# cc1101-2ch-dimmer.net
KiCad netlist of a schematic drawn in EAGLE
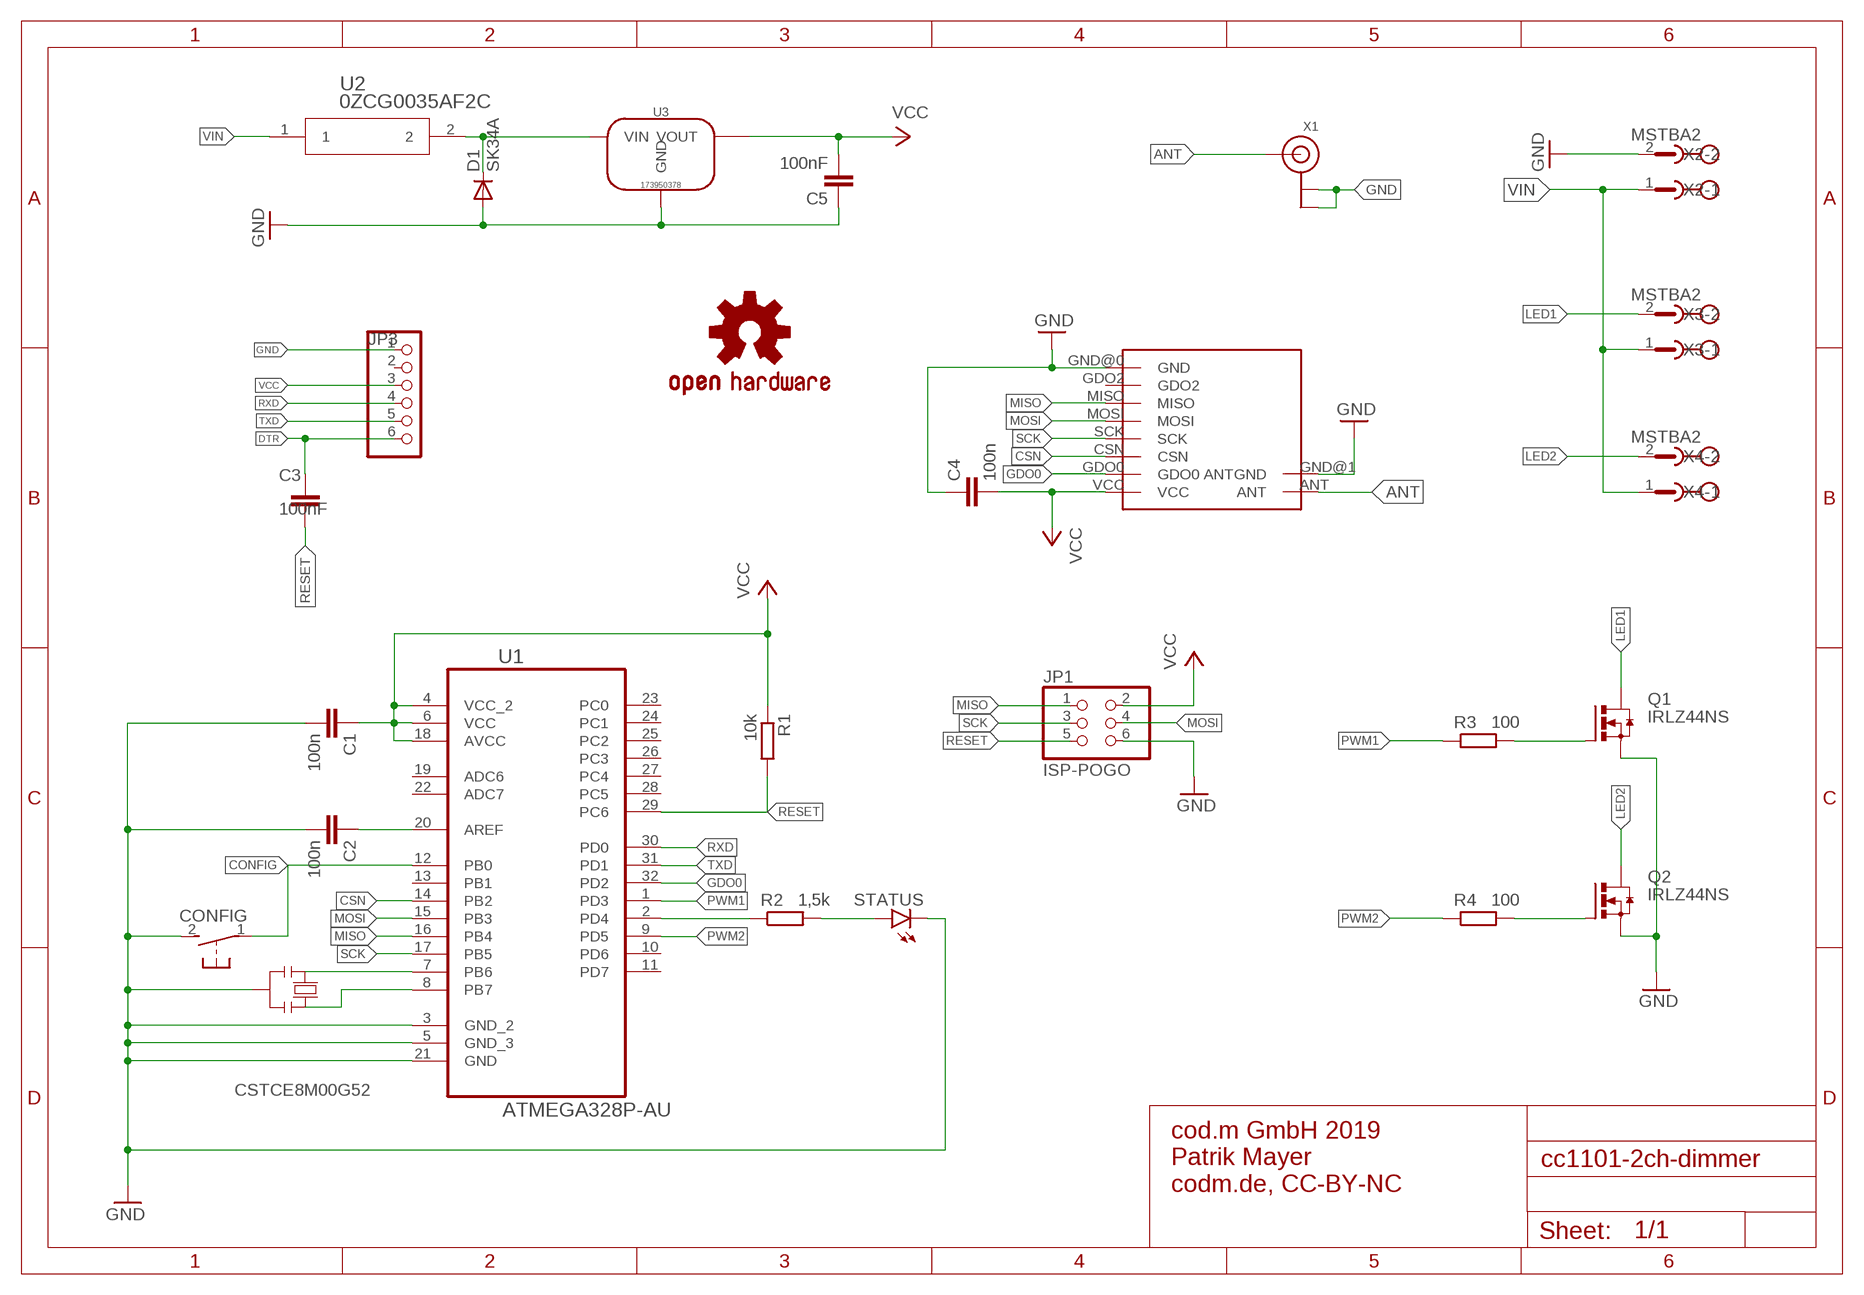
[diagram p0: schematic, sheet 1]

(export (version "E")
  (design (tool "Eeschema 10.0.6"))
  (components
    (comp (ref "C1")
      (value "100n")
      (footprint "eagle-import:C0805")
      (libsource (lib "eagle-import") (part "C-EUC0805"))
    )
    (comp (ref "C2")
      (value "100n")
      (footprint "eagle-import:C0805")
      (libsource (lib "eagle-import") (part "C-EUC0805"))
    )
    (comp (ref "C3")
      (value "100nF")
      (footprint "eagle-import:C0805")
      (libsource (lib "eagle-import") (part "C-EUC0805"))
    )
    (comp (ref "C4")
      (value "100n")
      (footprint "eagle-import:C0805")
      (libsource (lib "eagle-import") (part "C-EUC0805"))
    )
    (comp (ref "C5")
      (value "100nF")
      (footprint "eagle-import:C0805")
      (libsource (lib "eagle-import") (part "C-EUC0805"))
    )
    (comp (ref "CONFIG")
      (value "31-XX")
      (footprint "eagle-import:B3F-31XX")
      (fields (field (name "MPN") "B3F-3100"))
      (libsource (lib "eagle-import") (part "31-XX"))
    )
    (comp (ref "D1")
      (value "SK34A")
      (footprint "eagle-import:DO214AC")
      (libsource (lib "eagle-import") (part "DIODE-DO214AC"))
    )
    (comp (ref "JP1")
      (value "ISP-POGO")
      (footprint "eagle-import:2X03")
      (libsource (lib "eagle-import") (part "PINHD6-CLEAN"))
    )
    (comp (ref "JP3")
      (value "PINHD-1X6")
      (footprint "eagle-import:1X06")
      (libsource (lib "eagle-import") (part "PINHD-1X6"))
    )
    (comp (ref "LOGO1")
      (value "OSHW-LOGOM")
      (footprint "eagle-import:OSHW-LOGO-M")
      (libsource (lib "eagle-import") (part "OSHW-LOGOM"))
    )
    (comp (ref "Q1")
      (value "IRLZ44NS")
      (footprint "eagle-import:D2PAK")
      (libsource (lib "eagle-import") (part "IRLZ44NSD2PAK"))
    )
    (comp (ref "Q2")
      (value "IRLZ44NS")
      (footprint "eagle-import:D2PAK")
      (libsource (lib "eagle-import") (part "IRLZ44NSD2PAK"))
    )
    (comp (ref "R1")
      (value "10k")
      (footprint "eagle-import:R0805")
      (libsource (lib "eagle-import") (part "R-EU_R0805"))
    )
    (comp (ref "R2")
      (value "1,5k")
      (footprint "eagle-import:R0805")
      (libsource (lib "eagle-import") (part "R-EU_R0805"))
    )
    (comp (ref "R3")
      (value "100")
      (footprint "eagle-import:R0805")
      (libsource (lib "eagle-import") (part "R-EU_R0805"))
    )
    (comp (ref "R4")
      (value "100")
      (footprint "eagle-import:R0805")
      (libsource (lib "eagle-import") (part "R-EU_R0805"))
    )
    (comp (ref "STATUS")
      (value "LEDCHIPLED_0805")
      (footprint "eagle-import:CHIPLED_0805")
      (libsource (lib "eagle-import") (part "LEDCHIPLED_0805"))
    )
    (comp (ref "U$1")
      (value "CC1101-868MS10")
      (footprint "eagle-import:CC1101-868MS10")
      (libsource (lib "eagle-import") (part "CC1101-868MS10"))
    )
    (comp (ref "U1")
      (value "ATMEGA328P-AU")
      (footprint "eagle-import:QFP80P900X900X120-32N")
      (libsource (lib "eagle-import") (part "ATMEGA328P-AU"))
    )
    (comp (ref "U2")
      (value "0ZCG0035AF2C")
      (footprint "eagle-import:0ZCG")
      (libsource (lib "eagle-import") (part "0ZCG0035AF2C"))
    )
    (comp (ref "U3")
      (value "173950378")
      (footprint "eagle-import:SIP-3")
      (fields (field (name "MF") "Wurth Electronics"))
      (libsource (lib "eagle-import") (part "173950378"))
    )
    (comp (ref "X1")
      (value "ANTENNA_U.FL")
      (footprint "eagle-import:U.FL")
      (libsource (lib "eagle-import") (part "ANTENNA_U.FL"))
    )
    (comp (ref "X2")
      (value "MSTBA2")
      (footprint "eagle-import:MSTBA2")
      (fields (field (name "MF") "FARNELL") (field (name "MPN") "1757242"))
      (libsource (lib "eagle-import") (part "MSTBA2"))
    )
    (comp (ref "X3")
      (value "MSTBA2")
      (footprint "eagle-import:MSTBA2")
      (fields (field (name "MF") "FARNELL") (field (name "MPN") "1757242"))
      (libsource (lib "eagle-import") (part "MSTBA2"))
    )
    (comp (ref "X4")
      (value "MSTBA2")
      (footprint "eagle-import:MSTBA2")
      (fields (field (name "MF") "FARNELL") (field (name "MPN") "1757242"))
      (libsource (lib "eagle-import") (part "MSTBA2"))
    )
    (comp (ref "Y1")
      (value "CSTCE8M00G52")
      (footprint "eagle-import:RESONATOR")
      (libsource (lib "eagle-import") (part "RESONATORMU"))
    )
  )
  (nets
    (net (code "1") (name "ANT") (class "Default")
      (node (ref "U$1") (pin "ANT") (pinfunction "ANT_ANT") (pintype "bidirectional"))
      (node (ref "X1") (pin "3") (pinfunction "SIGNAL_3") (pintype "passive"))
    )
    (net (code "2") (name "CONFIG") (class "Default")
      (node (ref "CONFIG") (pin "1") (pinfunction "P_1") (pintype "passive"))
      (node (ref "U1") (pin "12") (pinfunction "PB0_12") (pintype "bidirectional"))
    )
    (net (code "3") (name "CSN") (class "Default")
      (node (ref "U$1") (pin "CSN") (pinfunction "CSN_CSN") (pintype "bidirectional"))
      (node (ref "U1") (pin "14") (pinfunction "PB2_14") (pintype "bidirectional"))
    )
    (net (code "4") (name "DTR") (class "Default")
      (node (ref "C3") (pin "1") (pinfunction "1_1") (pintype "passive"))
      (node (ref "JP3") (pin "6") (pinfunction "6_6") (pintype "passive"))
    )
    (net (code "5") (name "GDO0") (class "Default")
      (node (ref "U$1") (pin "GDO0") (pinfunction "GDO0_GDO0") (pintype "bidirectional"))
      (node (ref "U1") (pin "32") (pinfunction "PD2_32") (pintype "bidirectional"))
    )
    (net (code "6") (name "GND") (class "Default")
      (node (ref "C1") (pin "2") (pinfunction "2_2") (pintype "passive"))
      (node (ref "C2") (pin "2") (pinfunction "2_2") (pintype "passive"))
      (node (ref "C4") (pin "1") (pinfunction "1_1") (pintype "passive"))
      (node (ref "C5") (pin "1") (pinfunction "1_1") (pintype "passive"))
      (node (ref "CONFIG") (pin "2") (pinfunction "S_2") (pintype "passive"))
      (node (ref "D1") (pin "A") (pinfunction "A_A") (pintype "passive"))
      (node (ref "JP1") (pin "6") (pinfunction "6_6") (pintype "passive"))
      (node (ref "JP3") (pin "1") (pinfunction "1_1") (pintype "passive"))
      (node (ref "Q1") (pin "3") (pinfunction "S_3") (pintype "passive"))
      (node (ref "Q2") (pin "3") (pinfunction "S_3") (pintype "passive"))
      (node (ref "STATUS") (pin "C") (pinfunction "C_C") (pintype "passive"))
      (node (ref "U$1") (pin "GND@0") (pinfunction "GND_GND@0") (pintype "bidirectional"))
      (node (ref "U$1") (pin "GND@1") (pinfunction "ANTGND_GND@1") (pintype "bidirectional"))
      (node (ref "U1") (pin "21") (pinfunction "GND_21") (pintype "passive"))
      (node (ref "U1") (pin "3") (pinfunction "GND_2_3") (pintype "passive"))
      (node (ref "U1") (pin "5") (pinfunction "GND_3_5") (pintype "passive"))
      (node (ref "U3") (pin "P$2") (pinfunction "GND_P$2") (pintype "bidirectional"))
      (node (ref "X1") (pin "1") (pinfunction "GND_1") (pintype "passive"))
      (node (ref "X1") (pin "2") (pinfunction "GND_2") (pintype "passive"))
      (node (ref "X2") (pin "2") (pinfunction "1_2") (pintype "passive"))
      (node (ref "Y1") (pin "2") (pinfunction "2_2") (pintype "passive"))
    )
    (net (code "7") (name "LED1") (class "Default")
      (node (ref "Q1") (pin "2") (pinfunction "D_2") (pintype "passive"))
      (node (ref "X3") (pin "2") (pinfunction "1_2") (pintype "passive"))
    )
    (net (code "8") (name "LED2") (class "Default")
      (node (ref "Q2") (pin "2") (pinfunction "D_2") (pintype "passive"))
      (node (ref "X4") (pin "2") (pinfunction "1_2") (pintype "passive"))
    )
    (net (code "9") (name "MISO") (class "Default")
      (node (ref "JP1") (pin "1") (pinfunction "1_1") (pintype "passive"))
      (node (ref "U$1") (pin "MISO") (pinfunction "MISO_MISO") (pintype "bidirectional"))
      (node (ref "U1") (pin "16") (pinfunction "PB4_16") (pintype "bidirectional"))
    )
    (net (code "10") (name "MOSI") (class "Default")
      (node (ref "JP1") (pin "4") (pinfunction "4_4") (pintype "passive"))
      (node (ref "U$1") (pin "MOSI") (pinfunction "MOSI_MOSI") (pintype "bidirectional"))
      (node (ref "U1") (pin "15") (pinfunction "PB3_15") (pintype "bidirectional"))
    )
    (net (code "11") (name "Net-(Q1-G)") (class "Default")
      (node (ref "Q1") (pin "1") (pinfunction "G_1") (pintype "passive"))
      (node (ref "R3") (pin "2") (pinfunction "2_2") (pintype "passive"))
    )
    (net (code "12") (name "Net-(Q2-G)") (class "Default")
      (node (ref "Q2") (pin "1") (pinfunction "G_1") (pintype "passive"))
      (node (ref "R4") (pin "2") (pinfunction "2_2") (pintype "passive"))
    )
    (net (code "13") (name "Net-(R2-Pad2)") (class "Default")
      (node (ref "R2") (pin "2") (pinfunction "2_2") (pintype "passive"))
      (node (ref "STATUS") (pin "A") (pinfunction "A_A") (pintype "passive"))
    )
    (net (code "14") (name "Net-(U1-AREF)") (class "Default")
      (node (ref "C2") (pin "1") (pinfunction "1_1") (pintype "passive"))
      (node (ref "U1") (pin "20") (pinfunction "AREF_20") (pintype "input"))
    )
    (net (code "15") (name "Net-(U1-PB6)") (class "Default")
      (node (ref "U1") (pin "7") (pinfunction "PB6_7") (pintype "bidirectional"))
      (node (ref "Y1") (pin "1") (pinfunction "1_1") (pintype "passive"))
    )
    (net (code "16") (name "Net-(U1-PB7)") (class "Default")
      (node (ref "U1") (pin "8") (pinfunction "PB7_8") (pintype "bidirectional"))
      (node (ref "Y1") (pin "3") (pinfunction "3_3") (pintype "passive"))
    )
    (net (code "17") (name "Net-(U1-PD4)") (class "Default")
      (node (ref "R2") (pin "1") (pinfunction "1_1") (pintype "passive"))
      (node (ref "U1") (pin "2") (pinfunction "PD4_2") (pintype "bidirectional"))
    )
    (net (code "18") (name "Net-(U3-VIN)") (class "Default")
      (node (ref "D1") (pin "C") (pinfunction "C_C") (pintype "passive"))
      (node (ref "U2") (pin "2") (pinfunction "2_2") (pintype "passive"))
      (node (ref "U3") (pin "P$1") (pinfunction "VIN_P$1") (pintype "bidirectional"))
    )
    (net (code "19") (name "PWM1") (class "Default")
      (node (ref "R3") (pin "1") (pinfunction "1_1") (pintype "passive"))
      (node (ref "U1") (pin "1") (pinfunction "PD3_1") (pintype "bidirectional"))
    )
    (net (code "20") (name "PWM2") (class "Default")
      (node (ref "R4") (pin "1") (pinfunction "1_1") (pintype "passive"))
      (node (ref "U1") (pin "9") (pinfunction "PD5_9") (pintype "bidirectional"))
    )
    (net (code "21") (name "RESET") (class "Default")
      (node (ref "C3") (pin "2") (pinfunction "2_2") (pintype "passive"))
      (node (ref "JP1") (pin "5") (pinfunction "5_5") (pintype "passive"))
      (node (ref "R1") (pin "2") (pinfunction "2_2") (pintype "passive"))
      (node (ref "U1") (pin "29") (pinfunction "PC6_29") (pintype "bidirectional"))
    )
    (net (code "22") (name "RXD") (class "Default")
      (node (ref "JP3") (pin "4") (pinfunction "4_4") (pintype "passive"))
      (node (ref "U1") (pin "30") (pinfunction "PD0_30") (pintype "bidirectional"))
    )
    (net (code "23") (name "SCK") (class "Default")
      (node (ref "JP1") (pin "3") (pinfunction "3_3") (pintype "passive"))
      (node (ref "U$1") (pin "SCK") (pinfunction "SCK_SCK") (pintype "bidirectional"))
      (node (ref "U1") (pin "17") (pinfunction "PB5_17") (pintype "bidirectional"))
    )
    (net (code "24") (name "TXD") (class "Default")
      (node (ref "JP3") (pin "5") (pinfunction "5_5") (pintype "passive"))
      (node (ref "U1") (pin "31") (pinfunction "PD1_31") (pintype "bidirectional"))
    )
    (net (code "25") (name "VCC") (class "Default")
      (node (ref "C1") (pin "1") (pinfunction "1_1") (pintype "passive"))
      (node (ref "C4") (pin "2") (pinfunction "2_2") (pintype "passive"))
      (node (ref "C5") (pin "2") (pinfunction "2_2") (pintype "passive"))
      (node (ref "JP1") (pin "2") (pinfunction "2_2") (pintype "passive"))
      (node (ref "JP3") (pin "3") (pinfunction "3_3") (pintype "passive"))
      (node (ref "R1") (pin "1") (pinfunction "1_1") (pintype "passive"))
      (node (ref "U$1") (pin "VCC") (pinfunction "VCC_VCC") (pintype "bidirectional"))
      (node (ref "U1") (pin "18") (pinfunction "AVCC_18") (pintype "power_in"))
      (node (ref "U1") (pin "4") (pinfunction "VCC_2_4") (pintype "power_in"))
      (node (ref "U1") (pin "6") (pinfunction "VCC_6") (pintype "power_in"))
      (node (ref "U3") (pin "P$3") (pinfunction "VOUT_P$3") (pintype "bidirectional"))
    )
    (net (code "26") (name "VIN") (class "Default")
      (node (ref "U2") (pin "1") (pinfunction "1_1") (pintype "passive"))
      (node (ref "X2") (pin "1") (pinfunction "1_1") (pintype "passive"))
      (node (ref "X3") (pin "1") (pinfunction "1_1") (pintype "passive"))
      (node (ref "X4") (pin "1") (pinfunction "1_1") (pintype "passive"))
    )
    (net (code "27") (name "unconnected-(JP3-Pad2)") (class "Default")
      (node (ref "JP3") (pin "2") (pinfunction "2_2") (pintype "passive"))
    )
    (net (code "28") (name "unconnected-(U$1-PadGDO2)") (class "Default")
      (node (ref "U$1") (pin "GDO2") (pinfunction "GDO2_GDO2") (pintype "bidirectional"))
    )
    (net (code "29") (name "unconnected-(U1-ADC6-Pad19)") (class "Default")
      (node (ref "U1") (pin "19") (pinfunction "ADC6_19") (pintype "input"))
    )
    (net (code "30") (name "unconnected-(U1-ADC7-Pad22)") (class "Default")
      (node (ref "U1") (pin "22") (pinfunction "ADC7_22") (pintype "input"))
    )
    (net (code "31") (name "unconnected-(U1-PB1-Pad13)") (class "Default")
      (node (ref "U1") (pin "13") (pinfunction "PB1_13") (pintype "bidirectional"))
    )
    (net (code "32") (name "unconnected-(U1-PC0-Pad23)") (class "Default")
      (node (ref "U1") (pin "23") (pinfunction "PC0_23") (pintype "bidirectional"))
    )
    (net (code "33") (name "unconnected-(U1-PC1-Pad24)") (class "Default")
      (node (ref "U1") (pin "24") (pinfunction "PC1_24") (pintype "bidirectional"))
    )
    (net (code "34") (name "unconnected-(U1-PC2-Pad25)") (class "Default")
      (node (ref "U1") (pin "25") (pinfunction "PC2_25") (pintype "bidirectional"))
    )
    (net (code "35") (name "unconnected-(U1-PC3-Pad26)") (class "Default")
      (node (ref "U1") (pin "26") (pinfunction "PC3_26") (pintype "bidirectional"))
    )
    (net (code "36") (name "unconnected-(U1-PC4-Pad27)") (class "Default")
      (node (ref "U1") (pin "27") (pinfunction "PC4_27") (pintype "bidirectional"))
    )
    (net (code "37") (name "unconnected-(U1-PC5-Pad28)") (class "Default")
      (node (ref "U1") (pin "28") (pinfunction "PC5_28") (pintype "bidirectional"))
    )
    (net (code "38") (name "unconnected-(U1-PD6-Pad10)") (class "Default")
      (node (ref "U1") (pin "10") (pinfunction "PD6_10") (pintype "bidirectional"))
    )
    (net (code "39") (name "unconnected-(U1-PD7-Pad11)") (class "Default")
      (node (ref "U1") (pin "11") (pinfunction "PD7_11") (pintype "bidirectional"))
    )
  )
)
